# DDR.net
KiCad netlist of a schematic drawn in Altium Designer
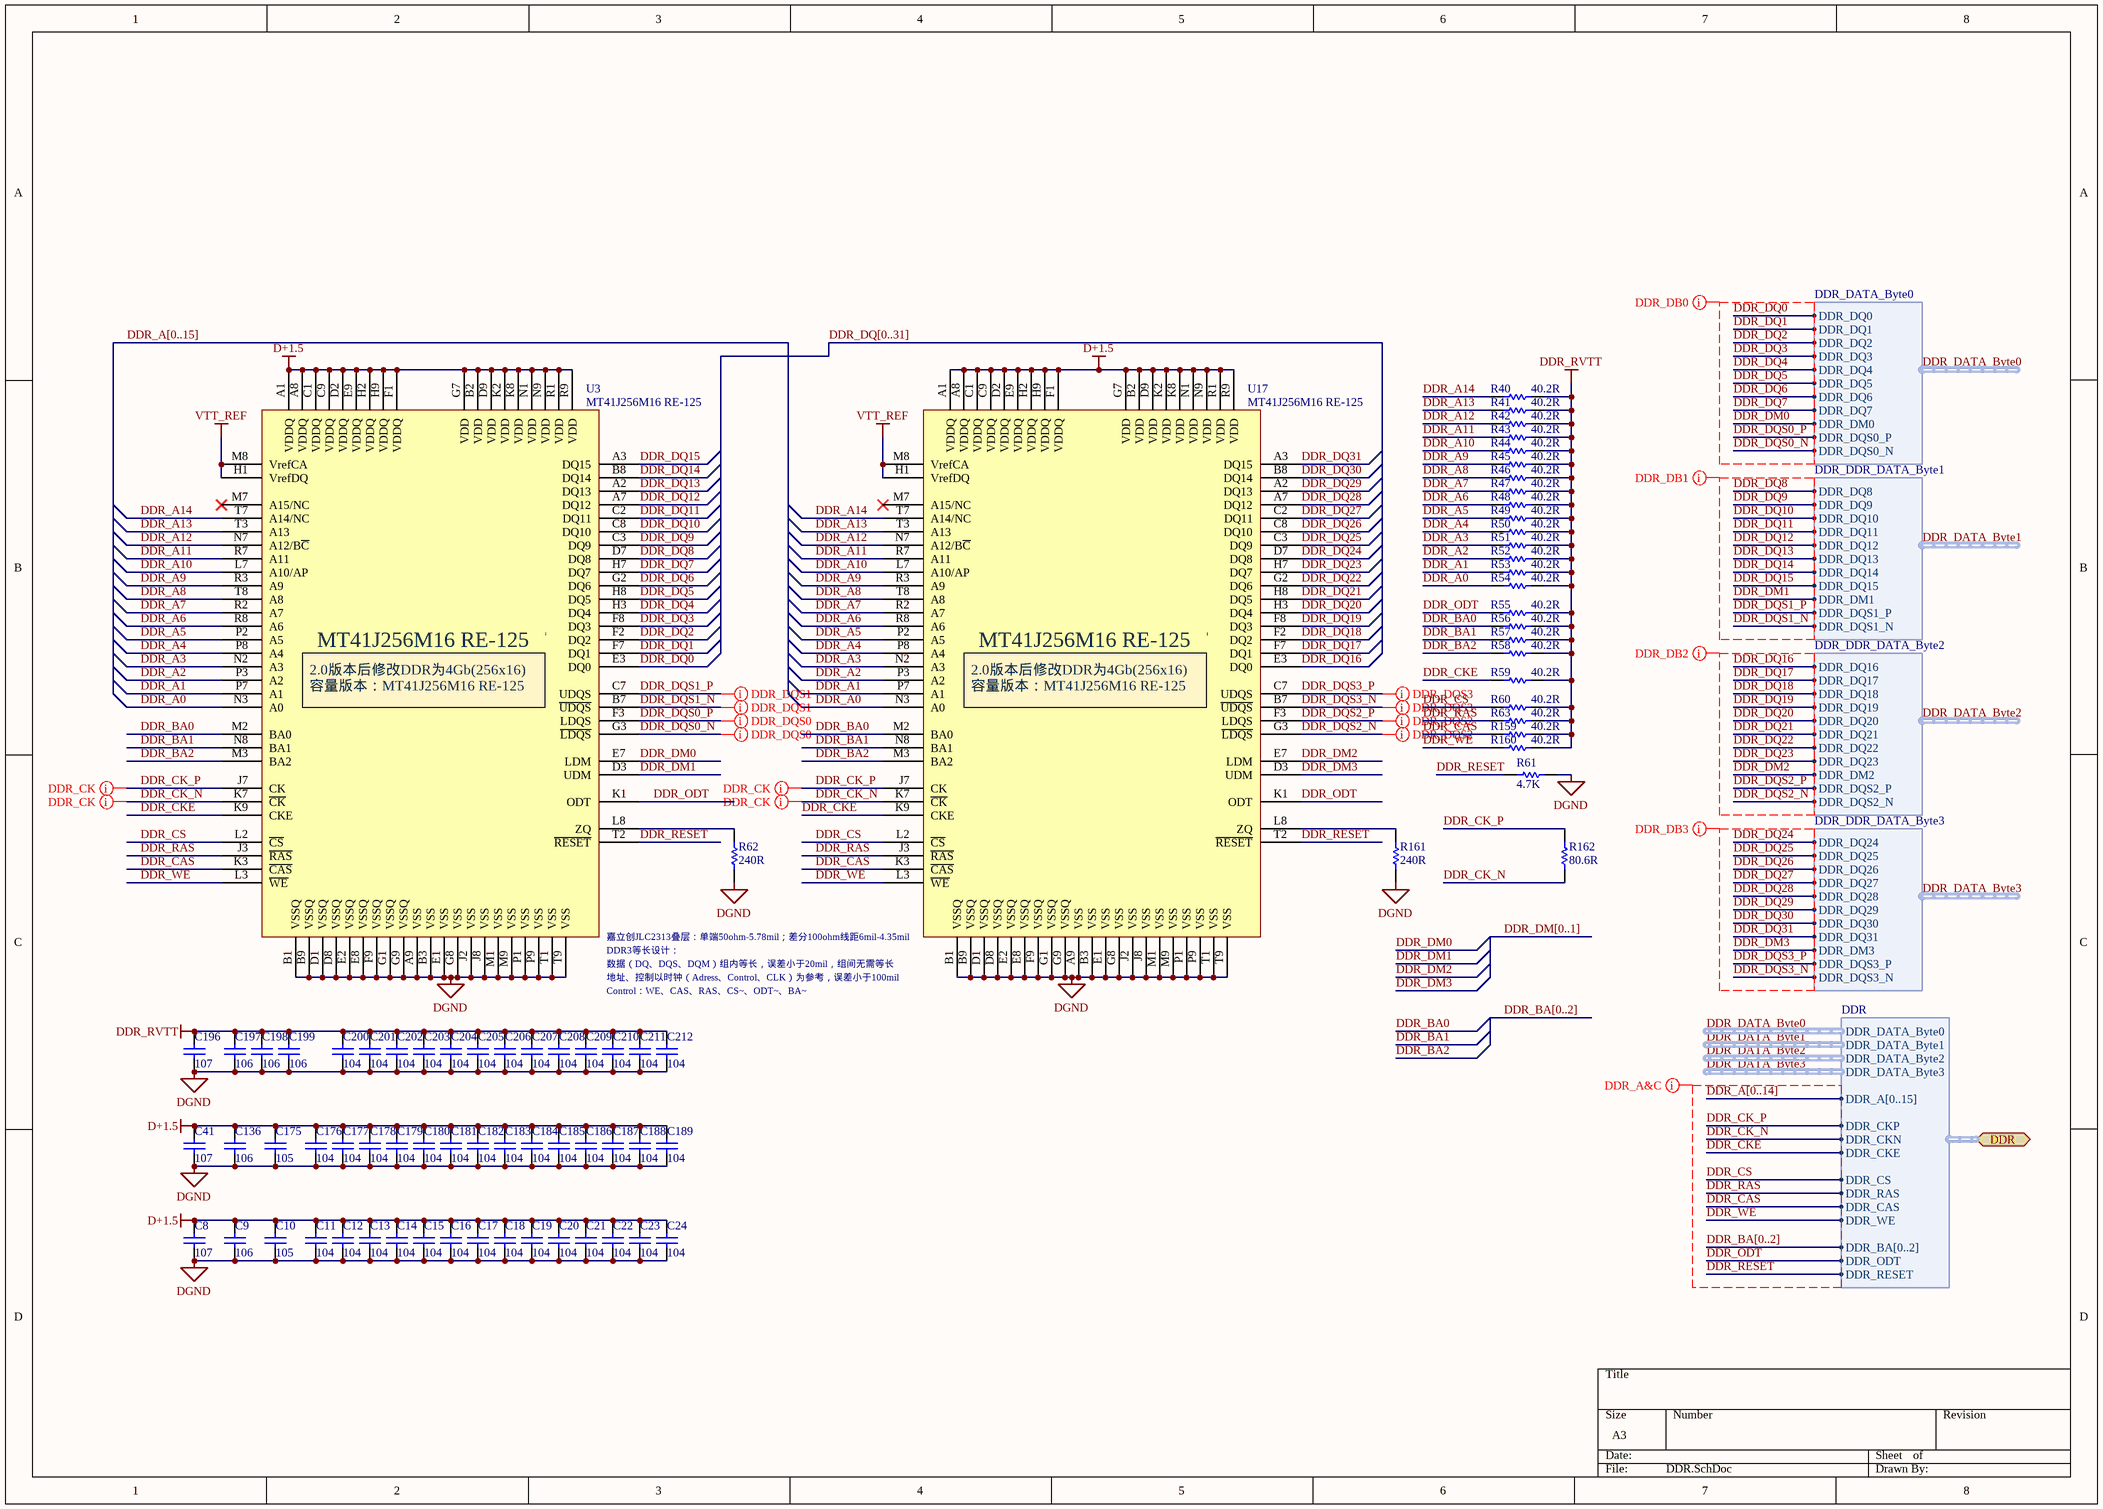
[diagram p0: DDR.SchDoc]

(export (version "E")
  (design (tool "Eeschema 10.0.6"))
  (components
    (comp (ref "C8")
      (value "107")
      (footprint "C 1206_L")
      (description "Capacitor")
      (fields (field (name "PUBLISHER") "Altium Limited"))
      (libsource (lib "Miscellaneous Devices") (part "Cap"))
    )
    (comp (ref "C9")
      (value "106")
      (footprint "C 0603_L")
      (description "Capacitor")
      (fields (field (name "PUBLISHER") "Altium Limited"))
      (libsource (lib "Miscellaneous Devices") (part "Cap"))
    )
    (comp (ref "C10")
      (value "105")
      (footprint "C 0603_L")
      (description "Capacitor")
      (fields (field (name "PUBLISHER") "Altium Limited"))
      (libsource (lib "Miscellaneous Devices") (part "Cap"))
    )
    (comp (ref "C11")
      (value "104")
      (footprint "C 0402_LL")
      (description "Capacitor")
      (fields (field (name "PUBLISHER") "Altium Limited"))
      (libsource (lib "Miscellaneous Devices") (part "Cap"))
    )
    (comp (ref "C12")
      (value "104")
      (footprint "C 0402_LL")
      (description "Capacitor")
      (fields (field (name "PUBLISHER") "Altium Limited"))
      (libsource (lib "Miscellaneous Devices") (part "Cap"))
    )
    (comp (ref "C13")
      (value "104")
      (footprint "C 0402_LL")
      (description "Capacitor")
      (fields (field (name "PUBLISHER") "Altium Limited"))
      (libsource (lib "Miscellaneous Devices") (part "Cap"))
    )
    (comp (ref "C14")
      (value "104")
      (footprint "C 0402_LL")
      (description "Capacitor")
      (fields (field (name "PUBLISHER") "Altium Limited"))
      (libsource (lib "Miscellaneous Devices") (part "Cap"))
    )
    (comp (ref "C15")
      (value "104")
      (footprint "C 0402_LL")
      (description "Capacitor")
      (fields (field (name "PUBLISHER") "Altium Limited"))
      (libsource (lib "Miscellaneous Devices") (part "Cap"))
    )
    (comp (ref "C16")
      (value "104")
      (footprint "C 0402_LL")
      (description "Capacitor")
      (fields (field (name "PUBLISHER") "Altium Limited"))
      (libsource (lib "Miscellaneous Devices") (part "Cap"))
    )
    (comp (ref "C17")
      (value "104")
      (footprint "C 0402_LL")
      (description "Capacitor")
      (fields (field (name "PUBLISHER") "Altium Limited"))
      (libsource (lib "Miscellaneous Devices") (part "Cap"))
    )
    (comp (ref "C18")
      (value "104")
      (footprint "C 0402_LL")
      (description "Capacitor")
      (fields (field (name "PUBLISHER") "Altium Limited"))
      (libsource (lib "Miscellaneous Devices") (part "Cap"))
    )
    (comp (ref "C19")
      (value "104")
      (footprint "C 0402_LL")
      (description "Capacitor")
      (fields (field (name "PUBLISHER") "Altium Limited"))
      (libsource (lib "Miscellaneous Devices") (part "Cap"))
    )
    (comp (ref "C20")
      (value "104")
      (footprint "C 0402_LL")
      (description "Capacitor")
      (fields (field (name "PUBLISHER") "Altium Limited"))
      (libsource (lib "Miscellaneous Devices") (part "Cap"))
    )
    (comp (ref "C21")
      (value "104")
      (footprint "C 0402_LL")
      (description "Capacitor")
      (fields (field (name "PUBLISHER") "Altium Limited"))
      (libsource (lib "Miscellaneous Devices") (part "Cap"))
    )
    (comp (ref "C22")
      (value "104")
      (footprint "C 0402_LL")
      (description "Capacitor")
      (fields (field (name "PUBLISHER") "Altium Limited"))
      (libsource (lib "Miscellaneous Devices") (part "Cap"))
    )
    (comp (ref "C23")
      (value "104")
      (footprint "C 0402_LL")
      (description "Capacitor")
      (fields (field (name "PUBLISHER") "Altium Limited"))
      (libsource (lib "Miscellaneous Devices") (part "Cap"))
    )
    (comp (ref "C24")
      (value "104")
      (footprint "C 0402_LL")
      (description "Capacitor")
      (fields (field (name "PUBLISHER") "Altium Limited"))
      (libsource (lib "Miscellaneous Devices") (part "Cap"))
    )
    (comp (ref "C41")
      (value "107")
      (footprint "C 1206_L")
      (description "Capacitor")
      (fields (field (name "PUBLISHER") "Altium Limited"))
      (libsource (lib "Miscellaneous Devices") (part "Cap"))
    )
    (comp (ref "C136")
      (value "106")
      (footprint "C 0603_L")
      (description "Capacitor")
      (fields (field (name "PUBLISHER") "Altium Limited"))
      (libsource (lib "Miscellaneous Devices") (part "Cap"))
    )
    (comp (ref "C175")
      (value "105")
      (footprint "C 0603_L")
      (description "Capacitor")
      (fields (field (name "PUBLISHER") "Altium Limited"))
      (libsource (lib "Miscellaneous Devices") (part "Cap"))
    )
    (comp (ref "C176")
      (value "104")
      (footprint "C 0402_LL")
      (description "Capacitor")
      (fields (field (name "PUBLISHER") "Altium Limited"))
      (libsource (lib "Miscellaneous Devices") (part "Cap"))
    )
    (comp (ref "C177")
      (value "104")
      (footprint "C 0402_LL")
      (description "Capacitor")
      (fields (field (name "PUBLISHER") "Altium Limited"))
      (libsource (lib "Miscellaneous Devices") (part "Cap"))
    )
    (comp (ref "C178")
      (value "104")
      (footprint "C 0402_LL")
      (description "Capacitor")
      (fields (field (name "PUBLISHER") "Altium Limited"))
      (libsource (lib "Miscellaneous Devices") (part "Cap"))
    )
    (comp (ref "C179")
      (value "104")
      (footprint "C 0402_LL")
      (description "Capacitor")
      (fields (field (name "PUBLISHER") "Altium Limited"))
      (libsource (lib "Miscellaneous Devices") (part "Cap"))
    )
    (comp (ref "C180")
      (value "104")
      (footprint "C 0402_LL")
      (description "Capacitor")
      (fields (field (name "PUBLISHER") "Altium Limited"))
      (libsource (lib "Miscellaneous Devices") (part "Cap"))
    )
    (comp (ref "C181")
      (value "104")
      (footprint "C 0402_LL")
      (description "Capacitor")
      (fields (field (name "PUBLISHER") "Altium Limited"))
      (libsource (lib "Miscellaneous Devices") (part "Cap"))
    )
    (comp (ref "C182")
      (value "104")
      (footprint "C 0402_LL")
      (description "Capacitor")
      (fields (field (name "PUBLISHER") "Altium Limited"))
      (libsource (lib "Miscellaneous Devices") (part "Cap"))
    )
    (comp (ref "C183")
      (value "104")
      (footprint "C 0402_LL")
      (description "Capacitor")
      (fields (field (name "PUBLISHER") "Altium Limited"))
      (libsource (lib "Miscellaneous Devices") (part "Cap"))
    )
    (comp (ref "C184")
      (value "104")
      (footprint "C 0402_LL")
      (description "Capacitor")
      (fields (field (name "PUBLISHER") "Altium Limited"))
      (libsource (lib "Miscellaneous Devices") (part "Cap"))
    )
    (comp (ref "C185")
      (value "104")
      (footprint "C 0402_LL")
      (description "Capacitor")
      (fields (field (name "PUBLISHER") "Altium Limited"))
      (libsource (lib "Miscellaneous Devices") (part "Cap"))
    )
    (comp (ref "C186")
      (value "104")
      (footprint "C 0402_LL")
      (description "Capacitor")
      (fields (field (name "PUBLISHER") "Altium Limited"))
      (libsource (lib "Miscellaneous Devices") (part "Cap"))
    )
    (comp (ref "C187")
      (value "104")
      (footprint "C 0402_LL")
      (description "Capacitor")
      (fields (field (name "PUBLISHER") "Altium Limited"))
      (libsource (lib "Miscellaneous Devices") (part "Cap"))
    )
    (comp (ref "C188")
      (value "104")
      (footprint "C 0402_LL")
      (description "Capacitor")
      (fields (field (name "PUBLISHER") "Altium Limited"))
      (libsource (lib "Miscellaneous Devices") (part "Cap"))
    )
    (comp (ref "C189")
      (value "104")
      (footprint "C 0402_LL")
      (description "Capacitor")
      (fields (field (name "PUBLISHER") "Altium Limited"))
      (libsource (lib "Miscellaneous Devices") (part "Cap"))
    )
    (comp (ref "C196")
      (value "107")
      (footprint "C 1206_L")
      (description "Capacitor")
      (fields (field (name "PUBLISHER") "Altium Limited"))
      (libsource (lib "Miscellaneous Devices") (part "Cap"))
    )
    (comp (ref "C197")
      (value "106")
      (footprint "C 0603_L")
      (description "Capacitor")
      (fields (field (name "PUBLISHER") "Altium Limited"))
      (libsource (lib "Miscellaneous Devices") (part "Cap"))
    )
    (comp (ref "C198")
      (value "106")
      (footprint "C 0603_L")
      (description "Capacitor")
      (fields (field (name "PUBLISHER") "Altium Limited"))
      (libsource (lib "Miscellaneous Devices") (part "Cap"))
    )
    (comp (ref "C199")
      (value "106")
      (footprint "C 0603_L")
      (description "Capacitor")
      (fields (field (name "PUBLISHER") "Altium Limited"))
      (libsource (lib "Miscellaneous Devices") (part "Cap"))
    )
    (comp (ref "C200")
      (value "104")
      (footprint "C 0402_LL")
      (description "Capacitor")
      (fields (field (name "PUBLISHER") "Altium Limited"))
      (libsource (lib "Miscellaneous Devices") (part "Cap"))
    )
    (comp (ref "C201")
      (value "104")
      (footprint "C 0402_LL")
      (description "Capacitor")
      (fields (field (name "PUBLISHER") "Altium Limited"))
      (libsource (lib "Miscellaneous Devices") (part "Cap"))
    )
    (comp (ref "C202")
      (value "104")
      (footprint "C 0402_LL")
      (description "Capacitor")
      (fields (field (name "PUBLISHER") "Altium Limited"))
      (libsource (lib "Miscellaneous Devices") (part "Cap"))
    )
    (comp (ref "C203")
      (value "104")
      (footprint "C 0402_LL")
      (description "Capacitor")
      (fields (field (name "PUBLISHER") "Altium Limited"))
      (libsource (lib "Miscellaneous Devices") (part "Cap"))
    )
    (comp (ref "C204")
      (value "104")
      (footprint "C 0402_LL")
      (description "Capacitor")
      (fields (field (name "PUBLISHER") "Altium Limited"))
      (libsource (lib "Miscellaneous Devices") (part "Cap"))
    )
    (comp (ref "C205")
      (value "104")
      (footprint "C 0402_LL")
      (description "Capacitor")
      (fields (field (name "PUBLISHER") "Altium Limited"))
      (libsource (lib "Miscellaneous Devices") (part "Cap"))
    )
    (comp (ref "C206")
      (value "104")
      (footprint "C 0402_LL")
      (description "Capacitor")
      (fields (field (name "PUBLISHER") "Altium Limited"))
      (libsource (lib "Miscellaneous Devices") (part "Cap"))
    )
    (comp (ref "C207")
      (value "104")
      (footprint "C 0402_LL")
      (description "Capacitor")
      (fields (field (name "PUBLISHER") "Altium Limited"))
      (libsource (lib "Miscellaneous Devices") (part "Cap"))
    )
    (comp (ref "C208")
      (value "104")
      (footprint "C 0402_LL")
      (description "Capacitor")
      (fields (field (name "PUBLISHER") "Altium Limited"))
      (libsource (lib "Miscellaneous Devices") (part "Cap"))
    )
    (comp (ref "C209")
      (value "104")
      (footprint "C 0402_LL")
      (description "Capacitor")
      (fields (field (name "PUBLISHER") "Altium Limited"))
      (libsource (lib "Miscellaneous Devices") (part "Cap"))
    )
    (comp (ref "C210")
      (value "104")
      (footprint "C 0402_LL")
      (description "Capacitor")
      (fields (field (name "PUBLISHER") "Altium Limited"))
      (libsource (lib "Miscellaneous Devices") (part "Cap"))
    )
    (comp (ref "C211")
      (value "104")
      (footprint "C 0402_LL")
      (description "Capacitor")
      (fields (field (name "PUBLISHER") "Altium Limited"))
      (libsource (lib "Miscellaneous Devices") (part "Cap"))
    )
    (comp (ref "C212")
      (value "104")
      (footprint "C 0402_LL")
      (description "Capacitor")
      (fields (field (name "PUBLISHER") "Altium Limited"))
      (libsource (lib "Miscellaneous Devices") (part "Cap"))
    )
    (comp (ref "R40")
      (value "40.2R")
      (footprint "R 0402_L")
      (description "Resistor")
      (fields (field (name "PUBLISHER") "Altium Limited"))
      (libsource (lib "Miscellaneous Devices") (part "Res1"))
    )
    (comp (ref "R41")
      (value "40.2R")
      (footprint "R 0402_L")
      (description "Resistor")
      (fields (field (name "PUBLISHER") "Altium Limited"))
      (libsource (lib "Miscellaneous Devices") (part "Res1"))
    )
    (comp (ref "R42")
      (value "40.2R")
      (footprint "R 0402_L")
      (description "Resistor")
      (fields (field (name "PUBLISHER") "Altium Limited"))
      (libsource (lib "Miscellaneous Devices") (part "Res1"))
    )
    (comp (ref "R43")
      (value "40.2R")
      (footprint "R 0402_L")
      (description "Resistor")
      (fields (field (name "PUBLISHER") "Altium Limited"))
      (libsource (lib "Miscellaneous Devices") (part "Res1"))
    )
    (comp (ref "R44")
      (value "40.2R")
      (footprint "R 0402_L")
      (description "Resistor")
      (fields (field (name "PUBLISHER") "Altium Limited"))
      (libsource (lib "Miscellaneous Devices") (part "Res1"))
    )
    (comp (ref "R45")
      (value "40.2R")
      (footprint "R 0402_L")
      (description "Resistor")
      (fields (field (name "PUBLISHER") "Altium Limited"))
      (libsource (lib "Miscellaneous Devices") (part "Res1"))
    )
    (comp (ref "R46")
      (value "40.2R")
      (footprint "R 0402_L")
      (description "Resistor")
      (fields (field (name "PUBLISHER") "Altium Limited"))
      (libsource (lib "Miscellaneous Devices") (part "Res1"))
    )
    (comp (ref "R47")
      (value "40.2R")
      (footprint "R 0402_L")
      (description "Resistor")
      (fields (field (name "PUBLISHER") "Altium Limited"))
      (libsource (lib "Miscellaneous Devices") (part "Res1"))
    )
    (comp (ref "R48")
      (value "40.2R")
      (footprint "R 0402_L")
      (description "Resistor")
      (fields (field (name "PUBLISHER") "Altium Limited"))
      (libsource (lib "Miscellaneous Devices") (part "Res1"))
    )
    (comp (ref "R49")
      (value "40.2R")
      (footprint "R 0402_L")
      (description "Resistor")
      (fields (field (name "PUBLISHER") "Altium Limited"))
      (libsource (lib "Miscellaneous Devices") (part "Res1"))
    )
    (comp (ref "R50")
      (value "40.2R")
      (footprint "R 0402_L")
      (description "Resistor")
      (fields (field (name "PUBLISHER") "Altium Limited"))
      (libsource (lib "Miscellaneous Devices") (part "Res1"))
    )
    (comp (ref "R51")
      (value "40.2R")
      (footprint "R 0402_L")
      (description "Resistor")
      (fields (field (name "PUBLISHER") "Altium Limited"))
      (libsource (lib "Miscellaneous Devices") (part "Res1"))
    )
    (comp (ref "R52")
      (value "40.2R")
      (footprint "R 0402_L")
      (description "Resistor")
      (fields (field (name "PUBLISHER") "Altium Limited"))
      (libsource (lib "Miscellaneous Devices") (part "Res1"))
    )
    (comp (ref "R53")
      (value "40.2R")
      (footprint "R 0402_L")
      (description "Resistor")
      (fields (field (name "PUBLISHER") "Altium Limited"))
      (libsource (lib "Miscellaneous Devices") (part "Res1"))
    )
    (comp (ref "R54")
      (value "40.2R")
      (footprint "R 0402_L")
      (description "Resistor")
      (fields (field (name "PUBLISHER") "Altium Limited"))
      (libsource (lib "Miscellaneous Devices") (part "Res1"))
    )
    (comp (ref "R55")
      (value "40.2R")
      (footprint "R 0402_L")
      (description "Resistor")
      (fields (field (name "PUBLISHER") "Altium Limited"))
      (libsource (lib "Miscellaneous Devices") (part "Res1"))
    )
    (comp (ref "R56")
      (value "40.2R")
      (footprint "R 0402_L")
      (description "Resistor")
      (fields (field (name "PUBLISHER") "Altium Limited"))
      (libsource (lib "Miscellaneous Devices") (part "Res1"))
    )
    (comp (ref "R57")
      (value "40.2R")
      (footprint "R 0402_L")
      (description "Resistor")
      (fields (field (name "PUBLISHER") "Altium Limited"))
      (libsource (lib "Miscellaneous Devices") (part "Res1"))
    )
    (comp (ref "R58")
      (value "40.2R")
      (footprint "R 0402_L")
      (description "Resistor")
      (fields (field (name "PUBLISHER") "Altium Limited"))
      (libsource (lib "Miscellaneous Devices") (part "Res1"))
    )
    (comp (ref "R59")
      (value "40.2R")
      (footprint "R 0402_L")
      (description "Resistor")
      (fields (field (name "PUBLISHER") "Altium Limited"))
      (libsource (lib "Miscellaneous Devices") (part "Res1"))
    )
    (comp (ref "R60")
      (value "40.2R")
      (footprint "R 0402_L")
      (description "Resistor")
      (fields (field (name "PUBLISHER") "Altium Limited"))
      (libsource (lib "Miscellaneous Devices") (part "Res1"))
    )
    (comp (ref "R61")
      (value "4.7K")
      (footprint "R 0402_L")
      (description "Resistor")
      (fields (field (name "PUBLISHER") "Altium Limited"))
      (libsource (lib "Miscellaneous Devices") (part "Res1"))
    )
    (comp (ref "R62")
      (value "240R")
      (footprint "R 0603_L")
      (description "Resistor")
      (fields (field (name "PUBLISHER") "Altium Limited"))
      (libsource (lib "Miscellaneous Devices") (part "Res1"))
    )
    (comp (ref "R63")
      (value "40.2R")
      (footprint "R 0402_L")
      (description "Resistor")
      (fields (field (name "PUBLISHER") "Altium Limited"))
      (libsource (lib "Miscellaneous Devices") (part "Res1"))
    )
    (comp (ref "R159")
      (value "40.2R")
      (footprint "R 0402_L")
      (description "Resistor")
      (fields (field (name "PUBLISHER") "Altium Limited"))
      (libsource (lib "Miscellaneous Devices") (part "Res1"))
    )
    (comp (ref "R160")
      (value "40.2R")
      (footprint "R 0402_L")
      (description "Resistor")
      (fields (field (name "PUBLISHER") "Altium Limited"))
      (libsource (lib "Miscellaneous Devices") (part "Res1"))
    )
    (comp (ref "R161")
      (value "240R")
      (footprint "R 0603_L")
      (description "Resistor")
      (fields (field (name "PUBLISHER") "Altium Limited"))
      (libsource (lib "Miscellaneous Devices") (part "Res1"))
    )
    (comp (ref "R162")
      (value "80.6R")
      (footprint "R 0402_L")
      (description "Resistor")
      (fields (field (name "PUBLISHER") "Altium Limited"))
      (libsource (lib "Miscellaneous Devices") (part "Res1"))
    )
    (comp (ref "U3")
      (value "MT41J256M16 RE-125")
      (footprint "FBGA96")
      (description "DDR3，存储芯片")
      (fields (field (name "MANUFACTURER") "Micron"))
      (libsource (lib "龙井V1") (part "MT41J128M16HA-125 IT"))
    )
    (comp (ref "U17")
      (value "MT41J256M16 RE-125")
      (footprint "FBGA96")
      (description "DDR3，存储芯片")
      (fields (field (name "MANUFACTURER") "Micron"))
      (libsource (lib "龙井V1") (part "MT41J128M16HA-125 IT"))
    )
  )
  (nets
    (net (code "11") (name "/DDR_A0") (class "Default")
      (node (ref "R54") (pin "1") (pinfunction "1_1") (pintype "passive"))
      (node (ref "U17") (pin "N3") (pinfunction "A0_N3") (pintype "passive"))
      (node (ref "U3") (pin "N3") (pinfunction "A0_N3") (pintype "passive"))
    )
    (net (code "12") (name "/DDR_A1") (class "Default")
      (node (ref "R53") (pin "1") (pinfunction "1_1") (pintype "passive"))
      (node (ref "U17") (pin "P7") (pinfunction "A1_P7") (pintype "passive"))
      (node (ref "U3") (pin "P7") (pinfunction "A1_P7") (pintype "passive"))
    )
    (net (code "13") (name "/DDR_A2") (class "Default")
      (node (ref "R52") (pin "1") (pinfunction "1_1") (pintype "passive"))
      (node (ref "U17") (pin "P3") (pinfunction "A2_P3") (pintype "passive"))
      (node (ref "U3") (pin "P3") (pinfunction "A2_P3") (pintype "passive"))
    )
    (net (code "14") (name "/DDR_A3") (class "Default")
      (node (ref "R51") (pin "1") (pinfunction "1_1") (pintype "passive"))
      (node (ref "U17") (pin "N2") (pinfunction "A3_N2") (pintype "passive"))
      (node (ref "U3") (pin "N2") (pinfunction "A3_N2") (pintype "passive"))
    )
    (net (code "15") (name "/DDR_A4") (class "Default")
      (node (ref "R50") (pin "1") (pinfunction "1_1") (pintype "passive"))
      (node (ref "U17") (pin "P8") (pinfunction "A4_P8") (pintype "passive"))
      (node (ref "U3") (pin "P8") (pinfunction "A4_P8") (pintype "passive"))
    )
    (net (code "16") (name "/DDR_A5") (class "Default")
      (node (ref "R49") (pin "1") (pinfunction "1_1") (pintype "passive"))
      (node (ref "U17") (pin "P2") (pinfunction "A5_P2") (pintype "passive"))
      (node (ref "U3") (pin "P2") (pinfunction "A5_P2") (pintype "passive"))
    )
    (net (code "17") (name "/DDR_A6") (class "Default")
      (node (ref "R48") (pin "1") (pinfunction "1_1") (pintype "passive"))
      (node (ref "U17") (pin "R8") (pinfunction "A6_R8") (pintype "passive"))
      (node (ref "U3") (pin "R8") (pinfunction "A6_R8") (pintype "passive"))
    )
    (net (code "18") (name "/DDR_A7") (class "Default")
      (node (ref "R47") (pin "1") (pinfunction "1_1") (pintype "passive"))
      (node (ref "U17") (pin "R2") (pinfunction "A7_R2") (pintype "passive"))
      (node (ref "U3") (pin "R2") (pinfunction "A7_R2") (pintype "passive"))
    )
    (net (code "19") (name "/DDR_A8") (class "Default")
      (node (ref "R46") (pin "1") (pinfunction "1_1") (pintype "passive"))
      (node (ref "U17") (pin "T8") (pinfunction "A8_T8") (pintype "passive"))
      (node (ref "U3") (pin "T8") (pinfunction "A8_T8") (pintype "passive"))
    )
    (net (code "20") (name "/DDR_A9") (class "Default")
      (node (ref "R45") (pin "1") (pinfunction "1_1") (pintype "passive"))
      (node (ref "U17") (pin "R3") (pinfunction "A9_R3") (pintype "passive"))
      (node (ref "U3") (pin "R3") (pinfunction "A9_R3") (pintype "passive"))
    )
    (net (code "21") (name "/DDR_A10") (class "Default")
      (node (ref "R44") (pin "1") (pinfunction "1_1") (pintype "passive"))
      (node (ref "U17") (pin "L7") (pinfunction "A10/AP_L7") (pintype "passive"))
      (node (ref "U3") (pin "L7") (pinfunction "A10/AP_L7") (pintype "passive"))
    )
    (net (code "22") (name "/DDR_A11") (class "Default")
      (node (ref "R43") (pin "1") (pinfunction "1_1") (pintype "passive"))
      (node (ref "U17") (pin "R7") (pinfunction "A11_R7") (pintype "passive"))
      (node (ref "U3") (pin "R7") (pinfunction "A11_R7") (pintype "passive"))
    )
    (net (code "23") (name "/DDR_A12") (class "Default")
      (node (ref "R42") (pin "1") (pinfunction "1_1") (pintype "passive"))
      (node (ref "U17") (pin "N7") (pinfunction "A12/B~{C}_N7") (pintype "passive"))
      (node (ref "U3") (pin "N7") (pinfunction "A12/B~{C}_N7") (pintype "passive"))
    )
    (net (code "24") (name "/DDR_A13") (class "Default")
      (node (ref "R41") (pin "1") (pinfunction "1_1") (pintype "passive"))
      (node (ref "U17") (pin "T3") (pinfunction "A13_T3") (pintype "passive"))
      (node (ref "U3") (pin "T3") (pinfunction "A13_T3") (pintype "passive"))
    )
    (net (code "25") (name "/DDR_A14") (class "Default")
      (node (ref "R40") (pin "1") (pinfunction "1_1") (pintype "passive"))
      (node (ref "U17") (pin "T7") (pinfunction "A14/NC_T7") (pintype "passive"))
      (node (ref "U3") (pin "T7") (pinfunction "A14/NC_T7") (pintype "passive"))
    )
    (net (code "28") (name "/DDR_BA0") (class "Default")
      (node (ref "R56") (pin "1") (pinfunction "1_1") (pintype "passive"))
      (node (ref "U17") (pin "M2") (pinfunction "BA0_M2") (pintype "passive"))
      (node (ref "U3") (pin "M2") (pinfunction "BA0_M2") (pintype "passive"))
    )
    (net (code "29") (name "/DDR_BA1") (class "Default")
      (node (ref "R57") (pin "1") (pinfunction "1_1") (pintype "passive"))
      (node (ref "U17") (pin "N8") (pinfunction "BA1_N8") (pintype "passive"))
      (node (ref "U3") (pin "N8") (pinfunction "BA1_N8") (pintype "passive"))
    )
    (net (code "30") (name "/DDR_BA2") (class "Default")
      (node (ref "R58") (pin "1") (pinfunction "1_1") (pintype "passive"))
      (node (ref "U17") (pin "M3") (pinfunction "BA2_M3") (pintype "passive"))
      (node (ref "U3") (pin "M3") (pinfunction "BA2_M3") (pintype "passive"))
    )
    (net (code "32") (name "/DDR_CAS") (class "Default")
      (node (ref "R159") (pin "1") (pinfunction "1_1") (pintype "passive"))
      (node (ref "U17") (pin "K3") (pinfunction "CAS_K3") (pintype "passive"))
      (node (ref "U3") (pin "K3") (pinfunction "CAS_K3") (pintype "passive"))
    )
    (net (code "33") (name "/DDR_CKE") (class "Default")
      (node (ref "R59") (pin "1") (pinfunction "1_1") (pintype "passive"))
      (node (ref "U17") (pin "K9") (pinfunction "CKE_K9") (pintype "passive"))
      (node (ref "U3") (pin "K9") (pinfunction "CKE_K9") (pintype "passive"))
    )
    (net (code "34") (name "/DDR_CK_N") (class "Default")
      (node (ref "R162") (pin "2") (pinfunction "2_2") (pintype "passive"))
      (node (ref "U17") (pin "K7") (pinfunction "CK_K7") (pintype "passive"))
      (node (ref "U3") (pin "K7") (pinfunction "CK_K7") (pintype "passive"))
    )
    (net (code "35") (name "/DDR_CK_P") (class "Default")
      (node (ref "R162") (pin "1") (pinfunction "1_1") (pintype "passive"))
      (node (ref "U17") (pin "J7") (pinfunction "CK_J7") (pintype "passive"))
      (node (ref "U3") (pin "J7") (pinfunction "CK_J7") (pintype "passive"))
    )
    (net (code "36") (name "/DDR_CS") (class "Default")
      (node (ref "R60") (pin "1") (pinfunction "1_1") (pintype "passive"))
      (node (ref "U17") (pin "L2") (pinfunction "CS_L2") (pintype "passive"))
      (node (ref "U3") (pin "L2") (pinfunction "CS_L2") (pintype "passive"))
    )
    (net (code "41") (name "/DDR_DM0") (class "Default")
      (node (ref "U3") (pin "E7") (pinfunction "LDM_E7") (pintype "passive"))
    )
    (net (code "42") (name "/DDR_DM1") (class "Default")
      (node (ref "U3") (pin "D3") (pinfunction "UDM_D3") (pintype "passive"))
    )
    (net (code "43") (name "/DDR_DM2") (class "Default")
      (node (ref "U17") (pin "E7") (pinfunction "LDM_E7") (pintype "passive"))
    )
    (net (code "44") (name "/DDR_DM3") (class "Default")
      (node (ref "U17") (pin "D3") (pinfunction "UDM_D3") (pintype "passive"))
    )
    (net (code "46") (name "/DDR_DQ0") (class "Default")
      (node (ref "U3") (pin "E3") (pinfunction "DQ0_E3") (pintype "passive"))
    )
    (net (code "47") (name "/DDR_DQ1") (class "Default")
      (node (ref "U3") (pin "F7") (pinfunction "DQ1_F7") (pintype "passive"))
    )
    (net (code "48") (name "/DDR_DQ2") (class "Default")
      (node (ref "U3") (pin "F2") (pinfunction "DQ2_F2") (pintype "passive"))
    )
    (net (code "49") (name "/DDR_DQ3") (class "Default")
      (node (ref "U3") (pin "F8") (pinfunction "DQ3_F8") (pintype "passive"))
    )
    (net (code "50") (name "/DDR_DQ4") (class "Default")
      (node (ref "U3") (pin "H3") (pinfunction "DQ4_H3") (pintype "passive"))
    )
    (net (code "51") (name "/DDR_DQ5") (class "Default")
      (node (ref "U3") (pin "H8") (pinfunction "DQ5_H8") (pintype "passive"))
    )
    (net (code "52") (name "/DDR_DQ6") (class "Default")
      (node (ref "U3") (pin "G2") (pinfunction "DQ6_G2") (pintype "passive"))
    )
    (net (code "53") (name "/DDR_DQ7") (class "Default")
      (node (ref "U3") (pin "H7") (pinfunction "DQ7_H7") (pintype "passive"))
    )
    (net (code "54") (name "/DDR_DQ8") (class "Default")
      (node (ref "U3") (pin "D7") (pinfunction "DQ8_D7") (pintype "passive"))
    )
    (net (code "55") (name "/DDR_DQ9") (class "Default")
      (node (ref "U3") (pin "C3") (pinfunction "DQ9_C3") (pintype "passive"))
    )
    (net (code "56") (name "/DDR_DQ10") (class "Default")
      (node (ref "U3") (pin "C8") (pinfunction "DQ10_C8") (pintype "passive"))
    )
    (net (code "57") (name "/DDR_DQ11") (class "Default")
      (node (ref "U3") (pin "C2") (pinfunction "DQ11_C2") (pintype "passive"))
    )
    (net (code "58") (name "/DDR_DQ12") (class "Default")
      (node (ref "U3") (pin "A7") (pinfunction "DQ12_A7") (pintype "passive"))
    )
    (net (code "59") (name "/DDR_DQ13") (class "Default")
      (node (ref "U3") (pin "A2") (pinfunction "DQ13_A2") (pintype "passive"))
    )
    (net (code "60") (name "/DDR_DQ14") (class "Default")
      (node (ref "U3") (pin "B8") (pinfunction "DQ14_B8") (pintype "passive"))
    )
    (net (code "61") (name "/DDR_DQ15") (class "Default")
      (node (ref "U3") (pin "A3") (pinfunction "DQ15_A3") (pintype "passive"))
    )
    (net (code "62") (name "/DDR_DQ16") (class "Default")
      (node (ref "U17") (pin "E3") (pinfunction "DQ0_E3") (pintype "passive"))
    )
    (net (code "63") (name "/DDR_DQ17") (class "Default")
      (node (ref "U17") (pin "F7") (pinfunction "DQ1_F7") (pintype "passive"))
    )
    (net (code "64") (name "/DDR_DQ18") (class "Default")
      (node (ref "U17") (pin "F2") (pinfunction "DQ2_F2") (pintype "passive"))
    )
    (net (code "65") (name "/DDR_DQ19") (class "Default")
      (node (ref "U17") (pin "F8") (pinfunction "DQ3_F8") (pintype "passive"))
    )
    (net (code "66") (name "/DDR_DQ20") (class "Default")
      (node (ref "U17") (pin "H3") (pinfunction "DQ4_H3") (pintype "passive"))
    )
    (net (code "67") (name "/DDR_DQ21") (class "Default")
      (node (ref "U17") (pin "H8") (pinfunction "DQ5_H8") (pintype "passive"))
    )
    (net (code "68") (name "/DDR_DQ22") (class "Default")
      (node (ref "U17") (pin "G2") (pinfunction "DQ6_G2") (pintype "passive"))
    )
    (net (code "69") (name "/DDR_DQ23") (class "Default")
      (node (ref "U17") (pin "H7") (pinfunction "DQ7_H7") (pintype "passive"))
    )
    (net (code "70") (name "/DDR_DQ24") (class "Default")
      (node (ref "U17") (pin "D7") (pinfunction "DQ8_D7") (pintype "passive"))
    )
    (net (code "71") (name "/DDR_DQ25") (class "Default")
      (node (ref "U17") (pin "C3") (pinfunction "DQ9_C3") (pintype "passive"))
    )
    (net (code "72") (name "/DDR_DQ26") (class "Default")
      (node (ref "U17") (pin "C8") (pinfunction "DQ10_C8") (pintype "passive"))
    )
    (net (code "73") (name "/DDR_DQ27") (class "Default")
      (node (ref "U17") (pin "C2") (pinfunction "DQ11_C2") (pintype "passive"))
    )
    (net (code "74") (name "/DDR_DQ28") (class "Default")
      (node (ref "U17") (pin "A7") (pinfunction "DQ12_A7") (pintype "passive"))
    )
    (net (code "75") (name "/DDR_DQ29") (class "Default")
      (node (ref "U17") (pin "A2") (pinfunction "DQ13_A2") (pintype "passive"))
    )
    (net (code "76") (name "/DDR_DQ30") (class "Default")
      (node (ref "U17") (pin "B8") (pinfunction "DQ14_B8") (pintype "passive"))
    )
    (net (code "77") (name "/DDR_DQ31") (class "Default")
      (node (ref "U17") (pin "A3") (pinfunction "DQ15_A3") (pintype "passive"))
    )
    (net (code "78") (name "/DDR_DQS0_N") (class "Default")
      (node (ref "U3") (pin "G3") (pinfunction "LDQS_G3") (pintype "passive"))
    )
    (net (code "79") (name "/DDR_DQS0_P") (class "Default")
      (node (ref "U3") (pin "F3") (pinfunction "LDQS_F3") (pintype "passive"))
    )
    (net (code "80") (name "/DDR_DQS1_N") (class "Default")
      (node (ref "U3") (pin "B7") (pinfunction "UDQS_B7") (pintype "passive"))
    )
    (net (code "81") (name "/DDR_DQS1_P") (class "Default")
      (node (ref "U3") (pin "C7") (pinfunction "UDQS_C7") (pintype "passive"))
    )
    (net (code "82") (name "/DDR_DQS2_N") (class "Default")
      (node (ref "U17") (pin "G3") (pinfunction "LDQS_G3") (pintype "passive"))
    )
    (net (code "83") (name "/DDR_DQS2_P") (class "Default")
      (node (ref "U17") (pin "F3") (pinfunction "LDQS_F3") (pintype "passive"))
    )
    (net (code "84") (name "/DDR_DQS3_N") (class "Default")
      (node (ref "U17") (pin "B7") (pinfunction "UDQS_B7") (pintype "passive"))
    )
    (net (code "85") (name "/DDR_DQS3_P") (class "Default")
      (node (ref "U17") (pin "C7") (pinfunction "UDQS_C7") (pintype "passive"))
    )
    (net (code "87") (name "/DDR_ODT") (class "Default")
      (node (ref "R55") (pin "2") (pinfunction "2_2") (pintype "passive"))
      (node (ref "U17") (pin "K1") (pinfunction "ODT_K1") (pintype "passive"))
      (node (ref "U3") (pin "K1") (pinfunction "ODT_K1") (pintype "passive"))
    )
    (net (code "88") (name "/DDR_RAS") (class "Default")
      (node (ref "R63") (pin "1") (pinfunction "1_1") (pintype "passive"))
      (node (ref "U17") (pin "J3") (pinfunction "RAS_J3") (pintype "passive"))
      (node (ref "U3") (pin "J3") (pinfunction "RAS_J3") (pintype "passive"))
    )
    (net (code "89") (name "/DDR_RESET") (class "Default")
      (node (ref "R61") (pin "2") (pinfunction "2_2") (pintype "passive"))
      (node (ref "U17") (pin "T2") (pinfunction "RESET_T2") (pintype "passive"))
      (node (ref "U3") (pin "T2") (pinfunction "RESET_T2") (pintype "passive"))
    )
    (net (code "90") (name "/DDR_WE") (class "Default")
      (node (ref "R160") (pin "1") (pinfunction "1_1") (pintype "passive"))
      (node (ref "U17") (pin "L3") (pinfunction "WE_L3") (pintype "passive"))
      (node (ref "U3") (pin "L3") (pinfunction "WE_L3") (pintype "passive"))
    )
    (net (code "96") (name "D+1.5") (class "Default")
      (node (ref "C10") (pin "2") (pinfunction "2_2") (pintype "passive"))
      (node (ref "C11") (pin "2") (pinfunction "2_2") (pintype "passive"))
      (node (ref "C12") (pin "2") (pinfunction "2_2") (pintype "passive"))
      (node (ref "C13") (pin "2") (pinfunction "2_2") (pintype "passive"))
      (node (ref "C136") (pin "2") (pinfunction "2_2") (pintype "passive"))
      (node (ref "C14") (pin "2") (pinfunction "2_2") (pintype "passive"))
      (node (ref "C15") (pin "2") (pinfunction "2_2") (pintype "passive"))
      (node (ref "C16") (pin "2") (pinfunction "2_2") (pintype "passive"))
      (node (ref "C17") (pin "2") (pinfunction "2_2") (pintype "passive"))
      (node (ref "C175") (pin "2") (pinfunction "2_2") (pintype "passive"))
      (node (ref "C176") (pin "2") (pinfunction "2_2") (pintype "passive"))
      (node (ref "C177") (pin "2") (pinfunction "2_2") (pintype "passive"))
      (node (ref "C178") (pin "2") (pinfunction "2_2") (pintype "passive"))
      (node (ref "C179") (pin "2") (pinfunction "2_2") (pintype "passive"))
      (node (ref "C18") (pin "2") (pinfunction "2_2") (pintype "passive"))
      (node (ref "C180") (pin "2") (pinfunction "2_2") (pintype "passive"))
      (node (ref "C181") (pin "2") (pinfunction "2_2") (pintype "passive"))
      (node (ref "C182") (pin "2") (pinfunction "2_2") (pintype "passive"))
      (node (ref "C183") (pin "2") (pinfunction "2_2") (pintype "passive"))
      (node (ref "C184") (pin "2") (pinfunction "2_2") (pintype "passive"))
      (node (ref "C185") (pin "2") (pinfunction "2_2") (pintype "passive"))
      (node (ref "C186") (pin "2") (pinfunction "2_2") (pintype "passive"))
      (node (ref "C187") (pin "2") (pinfunction "2_2") (pintype "passive"))
      (node (ref "C188") (pin "2") (pinfunction "2_2") (pintype "passive"))
      (node (ref "C189") (pin "2") (pinfunction "2_2") (pintype "passive"))
      (node (ref "C19") (pin "2") (pinfunction "2_2") (pintype "passive"))
      (node (ref "C20") (pin "2") (pinfunction "2_2") (pintype "passive"))
      (node (ref "C21") (pin "2") (pinfunction "2_2") (pintype "passive"))
      (node (ref "C22") (pin "2") (pinfunction "2_2") (pintype "passive"))
      (node (ref "C23") (pin "2") (pinfunction "2_2") (pintype "passive"))
      (node (ref "C24") (pin "2") (pinfunction "2_2") (pintype "passive"))
      (node (ref "C41") (pin "2") (pinfunction "2_2") (pintype "passive"))
      (node (ref "C8") (pin "2") (pinfunction "2_2") (pintype "passive"))
      (node (ref "C9") (pin "2") (pinfunction "2_2") (pintype "passive"))
      (node (ref "U17") (pin "A1") (pinfunction "VDDQ_A1") (pintype "passive"))
      (node (ref "U17") (pin "A8") (pinfunction "VDDQ_A8") (pintype "passive"))
      (node (ref "U17") (pin "B2") (pinfunction "VDD_B2") (pintype "passive"))
      (node (ref "U17") (pin "C1") (pinfunction "VDDQ_C1") (pintype "passive"))
      (node (ref "U17") (pin "C9") (pinfunction "VDDQ_C9") (pintype "passive"))
      (node (ref "U17") (pin "D2") (pinfunction "VDDQ_D2") (pintype "passive"))
      (node (ref "U17") (pin "D9") (pinfunction "VDD_D9") (pintype "passive"))
      (node (ref "U17") (pin "E9") (pinfunction "VDDQ_E9") (pintype "passive"))
      (node (ref "U17") (pin "F1") (pinfunction "VDDQ_F1") (pintype "passive"))
      (node (ref "U17") (pin "G7") (pinfunction "VDD_G7") (pintype "passive"))
      (node (ref "U17") (pin "H2") (pinfunction "VDDQ_H2") (pintype "passive"))
      (node (ref "U17") (pin "H9") (pinfunction "VDDQ_H9") (pintype "passive"))
      (node (ref "U17") (pin "K2") (pinfunction "VDD_K2") (pintype "passive"))
      (node (ref "U17") (pin "K8") (pinfunction "VDD_K8") (pintype "passive"))
      (node (ref "U17") (pin "N1") (pinfunction "VDD_N1") (pintype "passive"))
      (node (ref "U17") (pin "N9") (pinfunction "VDD_N9") (pintype "passive"))
      (node (ref "U17") (pin "R1") (pinfunction "VDD_R1") (pintype "passive"))
      (node (ref "U17") (pin "R9") (pinfunction "VDD_R9") (pintype "passive"))
      (node (ref "U3") (pin "A1") (pinfunction "VDDQ_A1") (pintype "passive"))
      (node (ref "U3") (pin "A8") (pinfunction "VDDQ_A8") (pintype "passive"))
      (node (ref "U3") (pin "B2") (pinfunction "VDD_B2") (pintype "passive"))
      (node (ref "U3") (pin "C1") (pinfunction "VDDQ_C1") (pintype "passive"))
      (node (ref "U3") (pin "C9") (pinfunction "VDDQ_C9") (pintype "passive"))
      (node (ref "U3") (pin "D2") (pinfunction "VDDQ_D2") (pintype "passive"))
      (node (ref "U3") (pin "D9") (pinfunction "VDD_D9") (pintype "passive"))
      (node (ref "U3") (pin "E9") (pinfunction "VDDQ_E9") (pintype "passive"))
      (node (ref "U3") (pin "F1") (pinfunction "VDDQ_F1") (pintype "passive"))
      (node (ref "U3") (pin "G7") (pinfunction "VDD_G7") (pintype "passive"))
      (node (ref "U3") (pin "H2") (pinfunction "VDDQ_H2") (pintype "passive"))
      (node (ref "U3") (pin "H9") (pinfunction "VDDQ_H9") (pintype "passive"))
      (node (ref "U3") (pin "K2") (pinfunction "VDD_K2") (pintype "passive"))
      (node (ref "U3") (pin "K8") (pinfunction "VDD_K8") (pintype "passive"))
      (node (ref "U3") (pin "N1") (pinfunction "VDD_N1") (pintype "passive"))
      (node (ref "U3") (pin "N9") (pinfunction "VDD_N9") (pintype "passive"))
      (node (ref "U3") (pin "R1") (pinfunction "VDD_R1") (pintype "passive"))
      (node (ref "U3") (pin "R9") (pinfunction "VDD_R9") (pintype "passive"))
    )
    (net (code "97") (name "DDR_RVTT") (class "Default")
      (node (ref "C196") (pin "2") (pinfunction "2_2") (pintype "passive"))
      (node (ref "C197") (pin "2") (pinfunction "2_2") (pintype "passive"))
      (node (ref "C198") (pin "2") (pinfunction "2_2") (pintype "passive"))
      (node (ref "C199") (pin "2") (pinfunction "2_2") (pintype "passive"))
      (node (ref "C200") (pin "2") (pinfunction "2_2") (pintype "passive"))
      (node (ref "C201") (pin "2") (pinfunction "2_2") (pintype "passive"))
      (node (ref "C202") (pin "2") (pinfunction "2_2") (pintype "passive"))
      (node (ref "C203") (pin "2") (pinfunction "2_2") (pintype "passive"))
      (node (ref "C204") (pin "2") (pinfunction "2_2") (pintype "passive"))
      (node (ref "C205") (pin "2") (pinfunction "2_2") (pintype "passive"))
      (node (ref "C206") (pin "2") (pinfunction "2_2") (pintype "passive"))
      (node (ref "C207") (pin "2") (pinfunction "2_2") (pintype "passive"))
      (node (ref "C208") (pin "2") (pinfunction "2_2") (pintype "passive"))
      (node (ref "C209") (pin "2") (pinfunction "2_2") (pintype "passive"))
      (node (ref "C210") (pin "2") (pinfunction "2_2") (pintype "passive"))
      (node (ref "C211") (pin "2") (pinfunction "2_2") (pintype "passive"))
      (node (ref "C212") (pin "2") (pinfunction "2_2") (pintype "passive"))
      (node (ref "R159") (pin "2") (pinfunction "2_2") (pintype "passive"))
      (node (ref "R160") (pin "2") (pinfunction "2_2") (pintype "passive"))
      (node (ref "R40") (pin "2") (pinfunction "2_2") (pintype "passive"))
      (node (ref "R41") (pin "2") (pinfunction "2_2") (pintype "passive"))
      (node (ref "R42") (pin "2") (pinfunction "2_2") (pintype "passive"))
      (node (ref "R43") (pin "2") (pinfunction "2_2") (pintype "passive"))
      (node (ref "R44") (pin "2") (pinfunction "2_2") (pintype "passive"))
      (node (ref "R45") (pin "2") (pinfunction "2_2") (pintype "passive"))
      (node (ref "R46") (pin "2") (pinfunction "2_2") (pintype "passive"))
      (node (ref "R47") (pin "2") (pinfunction "2_2") (pintype "passive"))
      (node (ref "R48") (pin "2") (pinfunction "2_2") (pintype "passive"))
      (node (ref "R49") (pin "2") (pinfunction "2_2") (pintype "passive"))
      (node (ref "R50") (pin "2") (pinfunction "2_2") (pintype "passive"))
      (node (ref "R51") (pin "2") (pinfunction "2_2") (pintype "passive"))
      (node (ref "R52") (pin "2") (pinfunction "2_2") (pintype "passive"))
      (node (ref "R53") (pin "2") (pinfunction "2_2") (pintype "passive"))
      (node (ref "R54") (pin "2") (pinfunction "2_2") (pintype "passive"))
      (node (ref "R55") (pin "1") (pinfunction "1_1") (pintype "passive"))
      (node (ref "R56") (pin "2") (pinfunction "2_2") (pintype "passive"))
      (node (ref "R57") (pin "2") (pinfunction "2_2") (pintype "passive"))
      (node (ref "R58") (pin "2") (pinfunction "2_2") (pintype "passive"))
      (node (ref "R59") (pin "2") (pinfunction "2_2") (pintype "passive"))
      (node (ref "R60") (pin "2") (pinfunction "2_2") (pintype "passive"))
      (node (ref "R63") (pin "2") (pinfunction "2_2") (pintype "passive"))
    )
    (net (code "98") (name "DGND") (class "Default")
      (node (ref "C10") (pin "1") (pinfunction "1_1") (pintype "passive"))
      (node (ref "C11") (pin "1") (pinfunction "1_1") (pintype "passive"))
      (node (ref "C12") (pin "1") (pinfunction "1_1") (pintype "passive"))
      (node (ref "C13") (pin "1") (pinfunction "1_1") (pintype "passive"))
      (node (ref "C136") (pin "1") (pinfunction "1_1") (pintype "passive"))
      (node (ref "C14") (pin "1") (pinfunction "1_1") (pintype "passive"))
      (node (ref "C15") (pin "1") (pinfunction "1_1") (pintype "passive"))
      (node (ref "C16") (pin "1") (pinfunction "1_1") (pintype "passive"))
      (node (ref "C17") (pin "1") (pinfunction "1_1") (pintype "passive"))
      (node (ref "C175") (pin "1") (pinfunction "1_1") (pintype "passive"))
      (node (ref "C176") (pin "1") (pinfunction "1_1") (pintype "passive"))
      (node (ref "C177") (pin "1") (pinfunction "1_1") (pintype "passive"))
      (node (ref "C178") (pin "1") (pinfunction "1_1") (pintype "passive"))
      (node (ref "C179") (pin "1") (pinfunction "1_1") (pintype "passive"))
      (node (ref "C18") (pin "1") (pinfunction "1_1") (pintype "passive"))
      (node (ref "C180") (pin "1") (pinfunction "1_1") (pintype "passive"))
      (node (ref "C181") (pin "1") (pinfunction "1_1") (pintype "passive"))
      (node (ref "C182") (pin "1") (pinfunction "1_1") (pintype "passive"))
      (node (ref "C183") (pin "1") (pinfunction "1_1") (pintype "passive"))
      (node (ref "C184") (pin "1") (pinfunction "1_1") (pintype "passive"))
      (node (ref "C185") (pin "1") (pinfunction "1_1") (pintype "passive"))
      (node (ref "C186") (pin "1") (pinfunction "1_1") (pintype "passive"))
      (node (ref "C187") (pin "1") (pinfunction "1_1") (pintype "passive"))
      (node (ref "C188") (pin "1") (pinfunction "1_1") (pintype "passive"))
      (node (ref "C189") (pin "1") (pinfunction "1_1") (pintype "passive"))
      (node (ref "C19") (pin "1") (pinfunction "1_1") (pintype "passive"))
      (node (ref "C196") (pin "1") (pinfunction "1_1") (pintype "passive"))
      (node (ref "C197") (pin "1") (pinfunction "1_1") (pintype "passive"))
      (node (ref "C198") (pin "1") (pinfunction "1_1") (pintype "passive"))
      (node (ref "C199") (pin "1") (pinfunction "1_1") (pintype "passive"))
      (node (ref "C20") (pin "1") (pinfunction "1_1") (pintype "passive"))
      (node (ref "C200") (pin "1") (pinfunction "1_1") (pintype "passive"))
      (node (ref "C201") (pin "1") (pinfunction "1_1") (pintype "passive"))
      (node (ref "C202") (pin "1") (pinfunction "1_1") (pintype "passive"))
      (node (ref "C203") (pin "1") (pinfunction "1_1") (pintype "passive"))
      (node (ref "C204") (pin "1") (pinfunction "1_1") (pintype "passive"))
      (node (ref "C205") (pin "1") (pinfunction "1_1") (pintype "passive"))
      (node (ref "C206") (pin "1") (pinfunction "1_1") (pintype "passive"))
      (node (ref "C207") (pin "1") (pinfunction "1_1") (pintype "passive"))
      (node (ref "C208") (pin "1") (pinfunction "1_1") (pintype "passive"))
      (node (ref "C209") (pin "1") (pinfunction "1_1") (pintype "passive"))
      (node (ref "C21") (pin "1") (pinfunction "1_1") (pintype "passive"))
      (node (ref "C210") (pin "1") (pinfunction "1_1") (pintype "passive"))
      (node (ref "C211") (pin "1") (pinfunction "1_1") (pintype "passive"))
      (node (ref "C212") (pin "1") (pinfunction "1_1") (pintype "passive"))
      (node (ref "C22") (pin "1") (pinfunction "1_1") (pintype "passive"))
      (node (ref "C23") (pin "1") (pinfunction "1_1") (pintype "passive"))
      (node (ref "C24") (pin "1") (pinfunction "1_1") (pintype "passive"))
      (node (ref "C41") (pin "1") (pinfunction "1_1") (pintype "passive"))
      (node (ref "C8") (pin "1") (pinfunction "1_1") (pintype "passive"))
      (node (ref "C9") (pin "1") (pinfunction "1_1") (pintype "passive"))
      (node (ref "R161") (pin "1") (pinfunction "1_1") (pintype "passive"))
      (node (ref "R61") (pin "1") (pinfunction "1_1") (pintype "passive"))
      (node (ref "R62") (pin "1") (pinfunction "1_1") (pintype "passive"))
      (node (ref "U17") (pin "A9") (pinfunction "VSS_A9") (pintype "passive"))
      (node (ref "U17") (pin "B1") (pinfunction "VSSQ_B1") (pintype "passive"))
      (node (ref "U17") (pin "B3") (pinfunction "VSS_B3") (pintype "passive"))
      (node (ref "U17") (pin "B9") (pinfunction "VSSQ_B9") (pintype "passive"))
      (node (ref "U17") (pin "D1") (pinfunction "VSSQ_D1") (pintype "passive"))
      (node (ref "U17") (pin "D8") (pinfunction "VSSQ_D8") (pintype "passive"))
      (node (ref "U17") (pin "E1") (pinfunction "VSS_E1") (pintype "passive"))
      (node (ref "U17") (pin "E2") (pinfunction "VSSQ_E2") (pintype "passive"))
      (node (ref "U17") (pin "E8") (pinfunction "VSSQ_E8") (pintype "passive"))
      (node (ref "U17") (pin "F9") (pinfunction "VSSQ_F9") (pintype "passive"))
      (node (ref "U17") (pin "G1") (pinfunction "VSSQ_G1") (pintype "passive"))
      (node (ref "U17") (pin "G8") (pinfunction "VSS_G8") (pintype "passive"))
      (node (ref "U17") (pin "G9") (pinfunction "VSSQ_G9") (pintype "passive"))
      (node (ref "U17") (pin "J2") (pinfunction "VSS_J2") (pintype "passive"))
      (node (ref "U17") (pin "J8") (pinfunction "VSS_J8") (pintype "passive"))
      (node (ref "U17") (pin "M1") (pinfunction "VSS_M1") (pintype "passive"))
      (node (ref "U17") (pin "M9") (pinfunction "VSS_M9") (pintype "passive"))
      (node (ref "U17") (pin "P1") (pinfunction "VSS_P1") (pintype "passive"))
      (node (ref "U17") (pin "P9") (pinfunction "VSS_P9") (pintype "passive"))
      (node (ref "U17") (pin "T1") (pinfunction "VSS_T1") (pintype "passive"))
      (node (ref "U17") (pin "T9") (pinfunction "VSS_T9") (pintype "passive"))
      (node (ref "U3") (pin "A9") (pinfunction "VSS_A9") (pintype "passive"))
      (node (ref "U3") (pin "B1") (pinfunction "VSSQ_B1") (pintype "passive"))
      (node (ref "U3") (pin "B3") (pinfunction "VSS_B3") (pintype "passive"))
      (node (ref "U3") (pin "B9") (pinfunction "VSSQ_B9") (pintype "passive"))
      (node (ref "U3") (pin "D1") (pinfunction "VSSQ_D1") (pintype "passive"))
      (node (ref "U3") (pin "D8") (pinfunction "VSSQ_D8") (pintype "passive"))
      (node (ref "U3") (pin "E1") (pinfunction "VSS_E1") (pintype "passive"))
      (node (ref "U3") (pin "E2") (pinfunction "VSSQ_E2") (pintype "passive"))
      (node (ref "U3") (pin "E8") (pinfunction "VSSQ_E8") (pintype "passive"))
      (node (ref "U3") (pin "F9") (pinfunction "VSSQ_F9") (pintype "passive"))
      (node (ref "U3") (pin "G1") (pinfunction "VSSQ_G1") (pintype "passive"))
      (node (ref "U3") (pin "G8") (pinfunction "VSS_G8") (pintype "passive"))
      (node (ref "U3") (pin "G9") (pinfunction "VSSQ_G9") (pintype "passive"))
      (node (ref "U3") (pin "J2") (pinfunction "VSS_J2") (pintype "passive"))
      (node (ref "U3") (pin "J8") (pinfunction "VSS_J8") (pintype "passive"))
      (node (ref "U3") (pin "M1") (pinfunction "VSS_M1") (pintype "passive"))
      (node (ref "U3") (pin "M9") (pinfunction "VSS_M9") (pintype "passive"))
      (node (ref "U3") (pin "P1") (pinfunction "VSS_P1") (pintype "passive"))
      (node (ref "U3") (pin "P9") (pinfunction "VSS_P9") (pintype "passive"))
      (node (ref "U3") (pin "T1") (pinfunction "VSS_T1") (pintype "passive"))
      (node (ref "U3") (pin "T9") (pinfunction "VSS_T9") (pintype "passive"))
    )
    (net (code "99") (name "Net-(U3-ZQ)") (class "Default")
      (node (ref "R62") (pin "2") (pinfunction "2_2") (pintype "passive"))
      (node (ref "U3") (pin "L8") (pinfunction "ZQ_L8") (pintype "passive"))
    )
    (net (code "100") (name "Net-(U17-ZQ)") (class "Default")
      (node (ref "R161") (pin "2") (pinfunction "2_2") (pintype "passive"))
      (node (ref "U17") (pin "L8") (pinfunction "ZQ_L8") (pintype "passive"))
    )
    (net (code "101") (name "VTT_REF") (class "Default")
      (node (ref "U17") (pin "H1") (pinfunction "VrefDQ_H1") (pintype "passive"))
      (node (ref "U17") (pin "M8") (pinfunction "VrefCA_M8") (pintype "passive"))
      (node (ref "U3") (pin "H1") (pinfunction "VrefDQ_H1") (pintype "passive"))
      (node (ref "U3") (pin "M8") (pinfunction "VrefCA_M8") (pintype "passive"))
    )
    (net (code "102") (name "unconnected-(U3-A15{slash}NC-PadM7)") (class "Default")
      (node (ref "U3") (pin "M7") (pinfunction "A15/NC_M7") (pintype "passive+no_connect"))
    )
    (net (code "103") (name "unconnected-(U3-PadJ1)") (class "Default")
      (node (ref "U3") (pin "J1") (pinfunction "J1_J1") (pintype "passive"))
    )
    (net (code "104") (name "unconnected-(U3-PadJ9)") (class "Default")
      (node (ref "U3") (pin "J9") (pinfunction "J9_J9") (pintype "passive"))
    )
    (net (code "105") (name "unconnected-(U3-PadL1)") (class "Default")
      (node (ref "U3") (pin "L1") (pinfunction "L1_L1") (pintype "passive"))
    )
    (net (code "106") (name "unconnected-(U3-PadL9)") (class "Default")
      (node (ref "U3") (pin "L9") (pinfunction "L9_L9") (pintype "passive"))
    )
    (net (code "107") (name "unconnected-(U17-A15{slash}NC-PadM7)") (class "Default")
      (node (ref "U17") (pin "M7") (pinfunction "A15/NC_M7") (pintype "passive+no_connect"))
    )
    (net (code "108") (name "unconnected-(U17-PadJ1)") (class "Default")
      (node (ref "U17") (pin "J1") (pinfunction "J1_J1") (pintype "passive"))
    )
    (net (code "109") (name "unconnected-(U17-PadJ9)") (class "Default")
      (node (ref "U17") (pin "J9") (pinfunction "J9_J9") (pintype "passive"))
    )
    (net (code "110") (name "unconnected-(U17-PadL1)") (class "Default")
      (node (ref "U17") (pin "L1") (pinfunction "L1_L1") (pintype "passive"))
    )
    (net (code "111") (name "unconnected-(U17-PadL9)") (class "Default")
      (node (ref "U17") (pin "L9") (pinfunction "L9_L9") (pintype "passive"))
    )
  )
)
